# ALLPRINT-CAPBOARD-677512-SIGNAL-OUTPUTS.net
KiCad netlist of a schematic drawn in Altium Designer
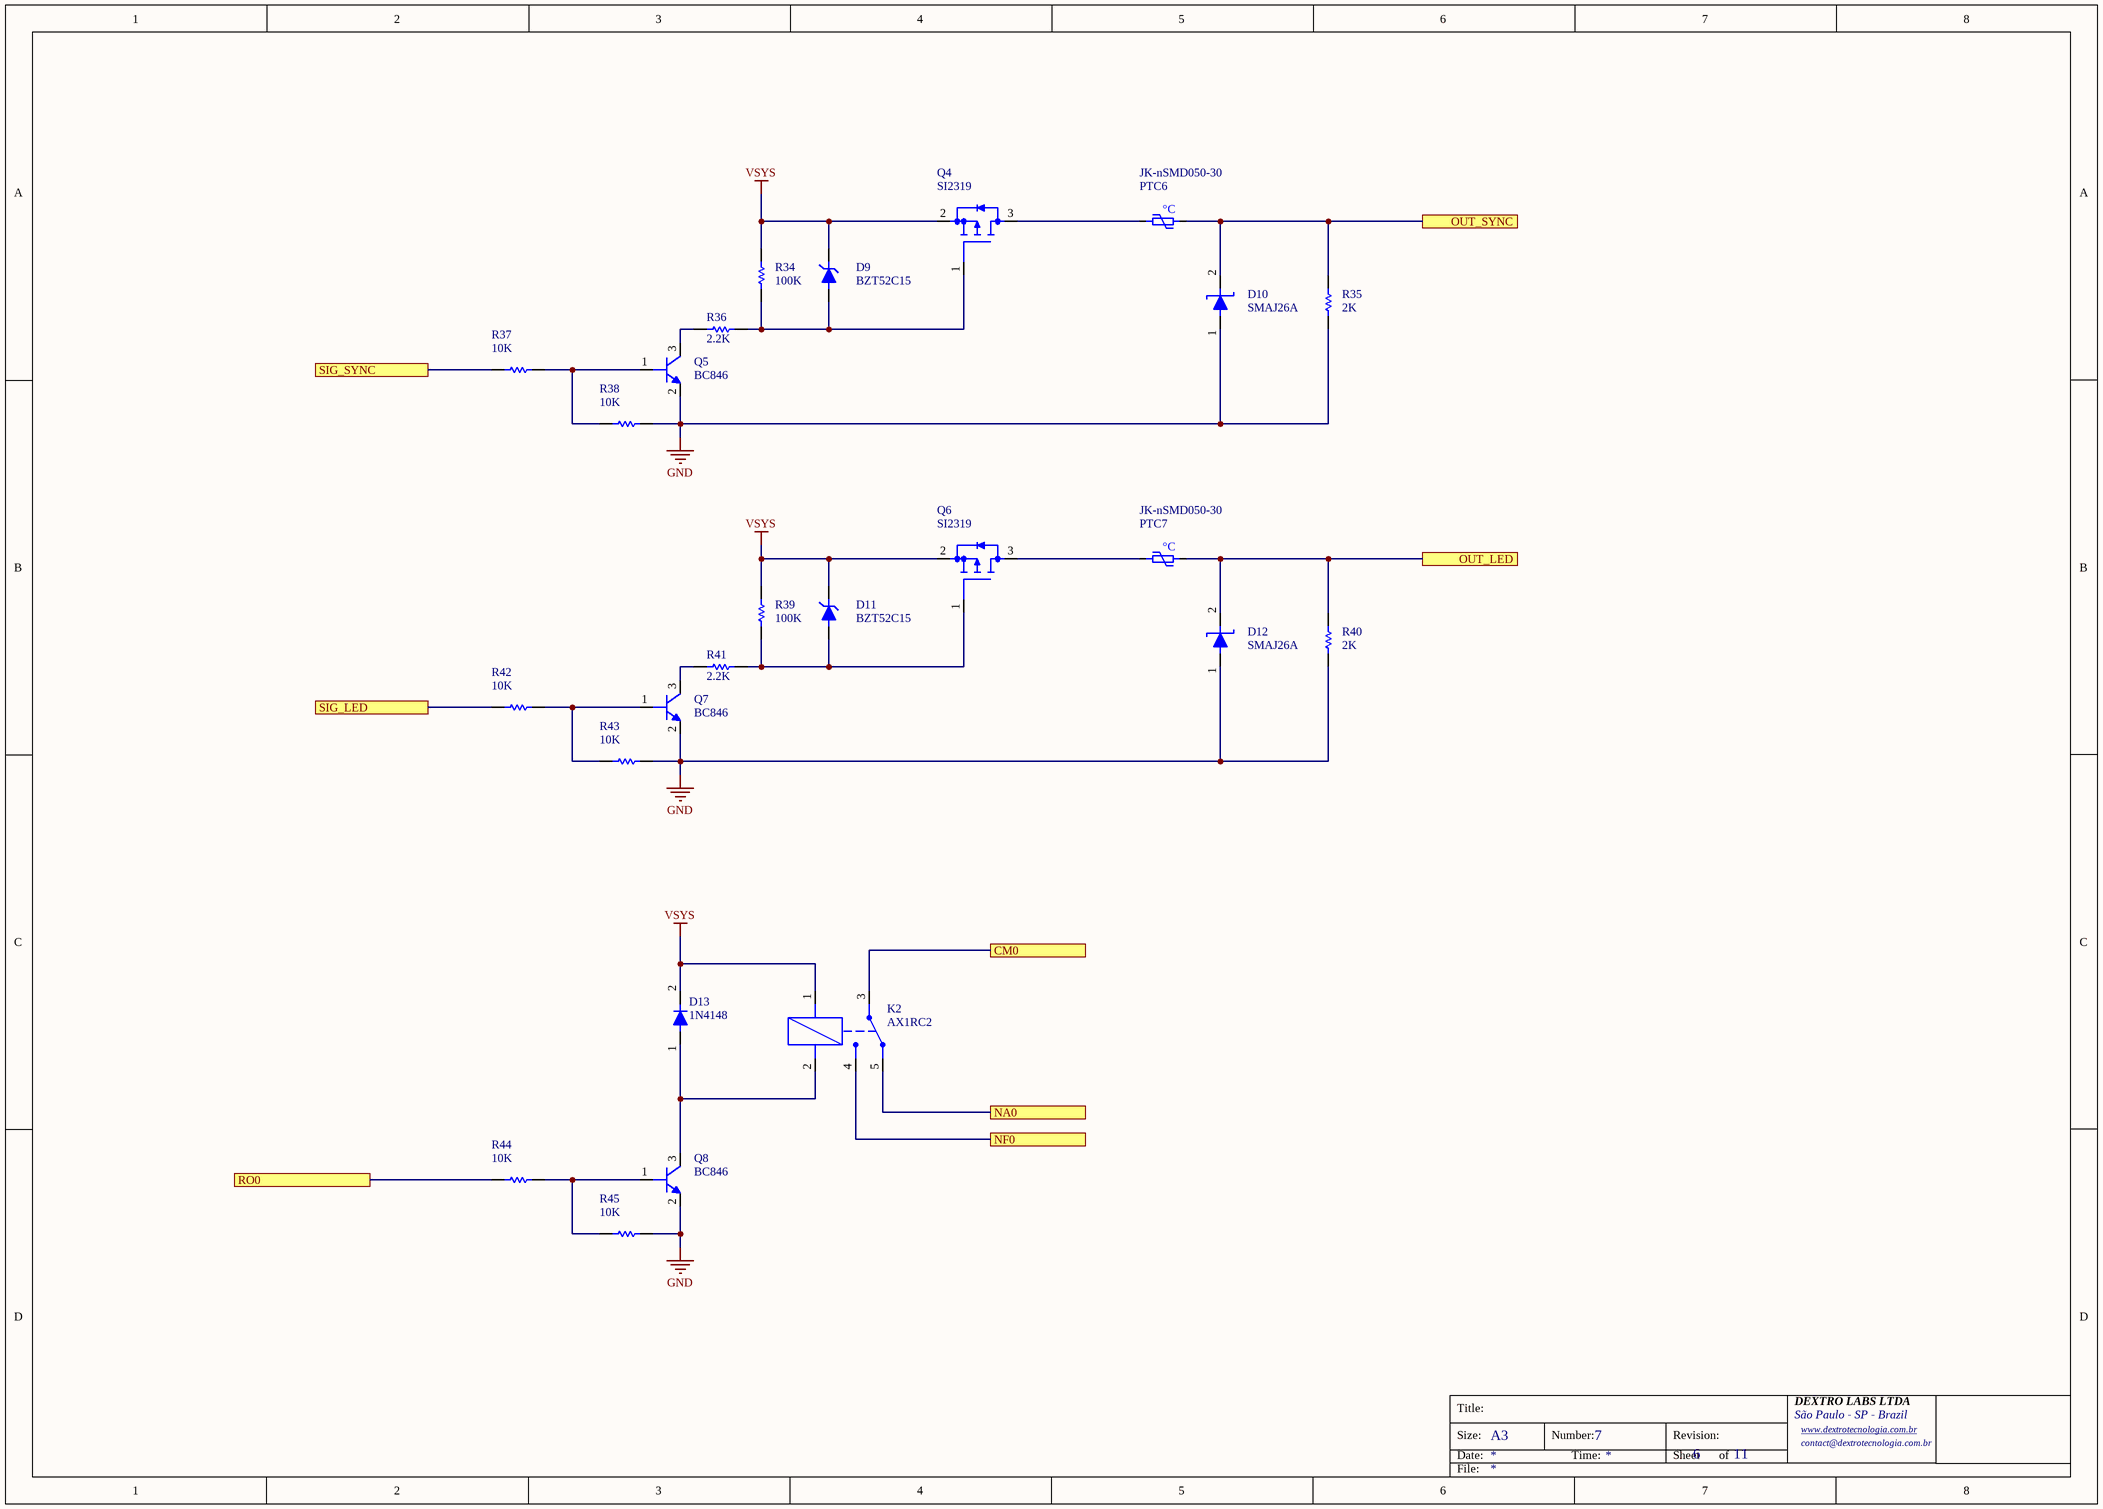
[diagram p0: ALLPRINT-CAPBOARD-677512-SIGNAL-OUTPUTS.SchDoc]

(export (version "E")
  (design (tool "Eeschema 10.0.6"))
  (components
    (comp (ref "D9")
      (value "BZT52C15")
      (footprint "SOD123")
      (description "DIODO ZENER 15V-500mW-SOD123")
      (libsource (lib "dextro-labs") (part "BZT52C15"))
    )
    (comp (ref "D10")
      (value "SMAJ26A")
      (footprint "DO214-AC (SMA)")
      (description "28.9V 26V 9.5A 42.1V 400W Unidirectional DO-214AC(SMA) TVS Diodes RoHS")
      (libsource (lib "dextro-labs") (part "SMAJ26A"))
    )
    (comp (ref "D11")
      (value "BZT52C15")
      (footprint "SOD123")
      (description "DIODO ZENER 15V-500mW-SOD123")
      (libsource (lib "dextro-labs") (part "BZT52C15"))
    )
    (comp (ref "D12")
      (value "SMAJ26A")
      (footprint "DO214-AC (SMA)")
      (description "28.9V 26V 9.5A 42.1V 400W Unidirectional DO-214AC(SMA) TVS Diodes RoHS")
      (libsource (lib "dextro-labs") (part "SMAJ26A"))
    )
    (comp (ref "D13")
      (value "1N4148")
      (footprint "SOD123")
      (description "1A 4ns 75V Independent 1V@50mA 150mA SOD-123 Single Diodes RoHS")
      (libsource (lib "dextro-labs") (part "1N4148"))
    )
    (comp (ref "K2")
      (value "AX1RC2")
      (footprint "METALTEX-AX1")
      (description "RELÉ-METALTEX-BOBINA 12V-15A-SPDT")
      (libsource (lib "dextro-labs") (part "AX1RC2"))
    )
    (comp (ref "PTC6")
      (value "JK-nSMD050-30")
      (footprint "PTC-1206")
      (description "30V 500mA 100A 1A 150mΩ 1206 PTC Resettable Fuses ROHS")
      (libsource (lib "dextro-labs") (part "PTC-FUSE-30V-500mA-1206"))
    )
    (comp (ref "PTC7")
      (value "JK-nSMD050-30")
      (footprint "PTC-1206")
      (description "30V 500mA 100A 1A 150mΩ 1206 PTC Resettable Fuses ROHS")
      (libsource (lib "dextro-labs") (part "PTC-FUSE-30V-500mA-1206"))
    )
    (comp (ref "Q4")
      (value "SI2319")
      (footprint "SOT23-3")
      (description "P-Channel 40V 5A 1.4W Surface Mount SOT-23")
      (libsource (lib "dextro-labs") (part "SI2319"))
    )
    (comp (ref "Q5")
      (value "BC846")
      (footprint "SOT23-3")
      (description "65V 200@10mA,5V 250mW 100mA NPN SOT-23 Bipolar (BJT) ROHS")
      (libsource (lib "dextro-labs") (part "TRANSISTOR-BC846B,215-SOT23"))
    )
    (comp (ref "Q6")
      (value "SI2319")
      (footprint "SOT23-3")
      (description "P-Channel 40V 5A 1.4W Surface Mount SOT-23")
      (libsource (lib "dextro-labs") (part "SI2319"))
    )
    (comp (ref "Q7")
      (value "BC846")
      (footprint "SOT23-3")
      (description "65V 200@10mA,5V 250mW 100mA NPN SOT-23 Bipolar (BJT) ROHS")
      (libsource (lib "dextro-labs") (part "TRANSISTOR-BC846B,215-SOT23"))
    )
    (comp (ref "Q8")
      (value "BC846")
      (footprint "SOT23-3")
      (description "65V 200@10mA,5V 250mW 100mA NPN SOT-23 Bipolar (BJT) ROHS")
      (libsource (lib "dextro-labs") (part "TRANSISTOR-BC846B,215-SOT23"))
    )
    (comp (ref "R34")
      (value "100K")
      (footprint "RES-0603")
      (description "100mW Thick Film Resistor 75V ±100ppm/℃ ±1% 100kΩ 0603 Chip Resistor - Surface Mount ROHS")
      (libsource (lib "dextro-labs") (part "RES-100K-1%-100mW-0603"))
    )
    (comp (ref "R35")
      (value "2K")
      (footprint "RES-1206")
      (description "250mW Thick Film Resistor 200V ±100ppm/℃ ±5% 2kΩ 1206 Chip Resistor - Surface Mount ROHS")
      (libsource (lib "dextro-labs") (part "RES-2K-1%-250mW-1206"))
    )
    (comp (ref "R36")
      (value "2.2K")
      (footprint "RES-0805")
      (description "125mW 2.2kΩ 150V ±100ppm/℃ Thick Film Resistor ±1% 0805 Chip Resistor - Surface Mount ROHS")
      (libsource (lib "dextro-labs") (part "RES-2.2K-1%-125mW-0805"))
    )
    (comp (ref "R37")
      (value "10K")
      (footprint "RES-0603")
      (description "100mW Thick Film Resistor 75V ±100ppm/℃ ±1% 10kΩ 0603 Chip Resistor - Surface Mount ROHS")
      (libsource (lib "dextro-labs") (part "RES-10K-1%-100mW-0603"))
    )
    (comp (ref "R38")
      (value "10K")
      (footprint "RES-0603")
      (description "100mW Thick Film Resistor 75V ±100ppm/℃ ±1% 10kΩ 0603 Chip Resistor - Surface Mount ROHS")
      (libsource (lib "dextro-labs") (part "RES-10K-1%-100mW-0603"))
    )
    (comp (ref "R39")
      (value "100K")
      (footprint "RES-0603")
      (description "100mW Thick Film Resistor 75V ±100ppm/℃ ±1% 100kΩ 0603 Chip Resistor - Surface Mount ROHS")
      (libsource (lib "dextro-labs") (part "RES-100K-1%-100mW-0603"))
    )
    (comp (ref "R40")
      (value "2K")
      (footprint "RES-1206")
      (description "250mW Thick Film Resistor 200V ±100ppm/℃ ±5% 2kΩ 1206 Chip Resistor - Surface Mount ROHS")
      (libsource (lib "dextro-labs") (part "RES-2K-1%-250mW-1206"))
    )
    (comp (ref "R41")
      (value "2.2K")
      (footprint "RES-0805")
      (description "125mW 2.2kΩ 150V ±100ppm/℃ Thick Film Resistor ±1% 0805 Chip Resistor - Surface Mount ROHS")
      (libsource (lib "dextro-labs") (part "RES-2.2K-1%-125mW-0805"))
    )
    (comp (ref "R42")
      (value "10K")
      (footprint "RES-0603")
      (description "100mW Thick Film Resistor 75V ±100ppm/℃ ±1% 10kΩ 0603 Chip Resistor - Surface Mount ROHS")
      (libsource (lib "dextro-labs") (part "RES-10K-1%-100mW-0603"))
    )
    (comp (ref "R43")
      (value "10K")
      (footprint "RES-0603")
      (description "100mW Thick Film Resistor 75V ±100ppm/℃ ±1% 10kΩ 0603 Chip Resistor - Surface Mount ROHS")
      (libsource (lib "dextro-labs") (part "RES-10K-1%-100mW-0603"))
    )
    (comp (ref "R44")
      (value "10K")
      (footprint "RES-0603")
      (description "100mW Thick Film Resistor 75V ±100ppm/℃ ±1% 10kΩ 0603 Chip Resistor - Surface Mount ROHS")
      (libsource (lib "dextro-labs") (part "RES-10K-1%-100mW-0603"))
    )
    (comp (ref "R45")
      (value "10K")
      (footprint "RES-0603")
      (description "100mW Thick Film Resistor 75V ±100ppm/℃ ±1% 10kΩ 0603 Chip Resistor - Surface Mount ROHS")
      (libsource (lib "dextro-labs") (part "RES-10K-1%-100mW-0603"))
    )
  )
  (nets
    (net (code "1") (name "/CM0") (class "Default")
      (node (ref "K2") (pin "3") (pinfunction "3_3") (pintype "passive"))
    )
    (net (code "2") (name "/NA0") (class "Default")
      (node (ref "K2") (pin "5") (pinfunction "5_5") (pintype "passive"))
    )
    (net (code "3") (name "/NF0") (class "Default")
      (node (ref "K2") (pin "4") (pinfunction "4_4") (pintype "passive"))
    )
    (net (code "4") (name "/OUT_LED") (class "Default")
      (node (ref "D12") (pin "2") (pinfunction "K_2") (pintype "passive"))
      (node (ref "PTC7") (pin "2") (pinfunction "2_2") (pintype "passive"))
      (node (ref "R40") (pin "2") (pinfunction "2_2") (pintype "passive"))
    )
    (net (code "5") (name "/OUT_SYNC") (class "Default")
      (node (ref "D10") (pin "2") (pinfunction "K_2") (pintype "passive"))
      (node (ref "PTC6") (pin "2") (pinfunction "2_2") (pintype "passive"))
      (node (ref "R35") (pin "2") (pinfunction "2_2") (pintype "passive"))
    )
    (net (code "6") (name "/RO0") (class "Default")
      (node (ref "R44") (pin "1") (pinfunction "1_1") (pintype "passive"))
    )
    (net (code "7") (name "/SIG_LED") (class "Default")
      (node (ref "R42") (pin "2") (pinfunction "2_2") (pintype "passive"))
    )
    (net (code "8") (name "/SIG_SYNC") (class "Default")
      (node (ref "R37") (pin "2") (pinfunction "2_2") (pintype "passive"))
    )
    (net (code "9") (name "GND") (class "Default")
      (node (ref "D10") (pin "1") (pinfunction "A_1") (pintype "passive"))
      (node (ref "D12") (pin "1") (pinfunction "A_1") (pintype "passive"))
      (node (ref "Q5") (pin "2") (pinfunction "2_2") (pintype "passive"))
      (node (ref "Q7") (pin "2") (pinfunction "2_2") (pintype "passive"))
      (node (ref "Q8") (pin "2") (pinfunction "2_2") (pintype "passive"))
      (node (ref "R35") (pin "1") (pinfunction "1_1") (pintype "passive"))
      (node (ref "R38") (pin "1") (pinfunction "1_1") (pintype "passive"))
      (node (ref "R40") (pin "1") (pinfunction "1_1") (pintype "passive"))
      (node (ref "R43") (pin "1") (pinfunction "1_1") (pintype "passive"))
      (node (ref "R45") (pin "2") (pinfunction "2_2") (pintype "passive"))
    )
    (net (code "10") (name "Net-(D13-A1)") (class "Default")
      (node (ref "D13") (pin "1") (pinfunction "A1_1") (pintype "passive"))
      (node (ref "K2") (pin "2") (pinfunction "2_2") (pintype "passive"))
      (node (ref "Q8") (pin "3") (pinfunction "3_3") (pintype "passive"))
    )
    (net (code "11") (name "Net-(Q4-D)") (class "Default")
      (node (ref "PTC6") (pin "1") (pinfunction "1_1") (pintype "passive"))
      (node (ref "Q4") (pin "3") (pinfunction "D_3") (pintype "passive"))
    )
    (net (code "12") (name "Net-(Q4-G])") (class "Default")
      (node (ref "D9") (pin "1") (pinfunction "1_1") (pintype "passive"))
      (node (ref "Q4") (pin "1") (pinfunction "G]_1") (pintype "passive"))
      (node (ref "R34") (pin "1") (pinfunction "1_1") (pintype "passive"))
      (node (ref "R36") (pin "1") (pinfunction "1_1") (pintype "passive"))
    )
    (net (code "13") (name "Net-(Q5-Pad1)") (class "Default")
      (node (ref "Q5") (pin "1") (pinfunction "1_1") (pintype "passive"))
      (node (ref "R37") (pin "1") (pinfunction "1_1") (pintype "passive"))
      (node (ref "R38") (pin "2") (pinfunction "2_2") (pintype "passive"))
    )
    (net (code "14") (name "Net-(Q5-Pad3)") (class "Default")
      (node (ref "Q5") (pin "3") (pinfunction "3_3") (pintype "passive"))
      (node (ref "R36") (pin "2") (pinfunction "2_2") (pintype "passive"))
    )
    (net (code "15") (name "Net-(Q6-D)") (class "Default")
      (node (ref "PTC7") (pin "1") (pinfunction "1_1") (pintype "passive"))
      (node (ref "Q6") (pin "3") (pinfunction "D_3") (pintype "passive"))
    )
    (net (code "16") (name "Net-(Q6-G])") (class "Default")
      (node (ref "D11") (pin "1") (pinfunction "1_1") (pintype "passive"))
      (node (ref "Q6") (pin "1") (pinfunction "G]_1") (pintype "passive"))
      (node (ref "R39") (pin "1") (pinfunction "1_1") (pintype "passive"))
      (node (ref "R41") (pin "1") (pinfunction "1_1") (pintype "passive"))
    )
    (net (code "17") (name "Net-(Q7-Pad1)") (class "Default")
      (node (ref "Q7") (pin "1") (pinfunction "1_1") (pintype "passive"))
      (node (ref "R42") (pin "1") (pinfunction "1_1") (pintype "passive"))
      (node (ref "R43") (pin "2") (pinfunction "2_2") (pintype "passive"))
    )
    (net (code "18") (name "Net-(Q7-Pad3)") (class "Default")
      (node (ref "Q7") (pin "3") (pinfunction "3_3") (pintype "passive"))
      (node (ref "R41") (pin "2") (pinfunction "2_2") (pintype "passive"))
    )
    (net (code "19") (name "Net-(Q8-Pad1)") (class "Default")
      (node (ref "Q8") (pin "1") (pinfunction "1_1") (pintype "passive"))
      (node (ref "R44") (pin "2") (pinfunction "2_2") (pintype "passive"))
      (node (ref "R45") (pin "1") (pinfunction "1_1") (pintype "passive"))
    )
    (net (code "20") (name "VSYS") (class "Default")
      (node (ref "D11") (pin "2") (pinfunction "2_2") (pintype "passive"))
      (node (ref "D13") (pin "2") (pinfunction "K_2") (pintype "passive"))
      (node (ref "D9") (pin "2") (pinfunction "2_2") (pintype "passive"))
      (node (ref "K2") (pin "1") (pinfunction "1_1") (pintype "passive"))
      (node (ref "Q4") (pin "2") (pinfunction "S_2") (pintype "passive"))
      (node (ref "Q6") (pin "2") (pinfunction "S_2") (pintype "passive"))
      (node (ref "R34") (pin "2") (pinfunction "2_2") (pintype "passive"))
      (node (ref "R39") (pin "2") (pinfunction "2_2") (pintype "passive"))
    )
  )
)
